# Electgpl_F883-6_THT_Rev1.net
KiCad netlist of a schematic drawn in EAGLE
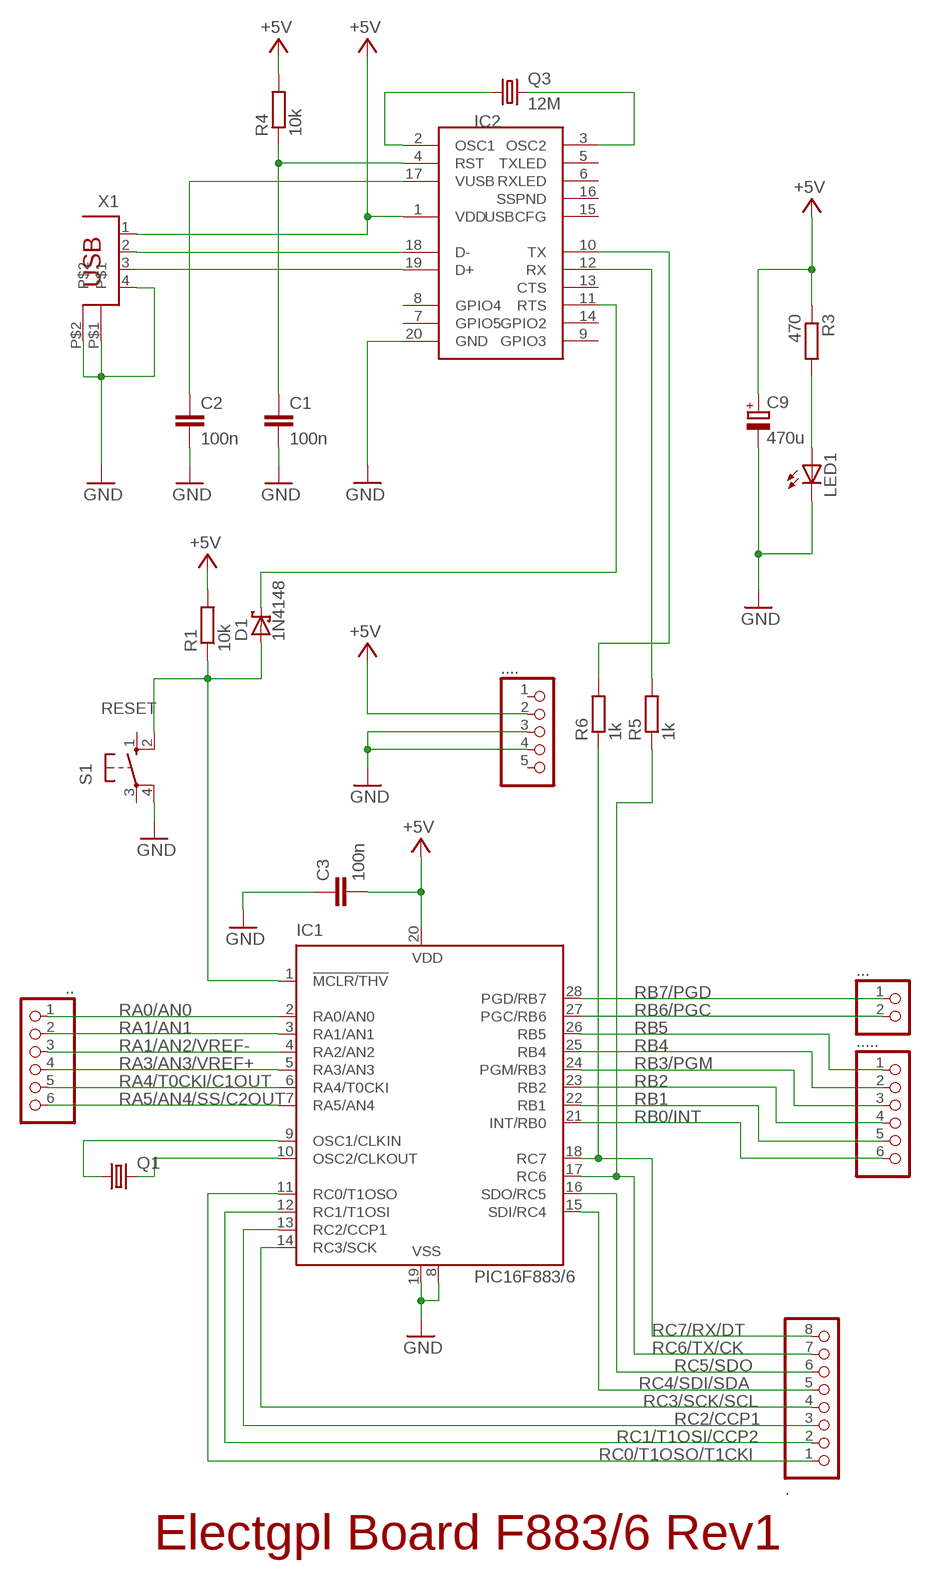
[diagram p0: schematic, sheet 1]

(export (version "E")
  (design (tool "Eeschema 10.0.6"))
  (components
    (comp (ref ".")
      (value "PINHD-1X8")
      (footprint "eagle-import:1X08")
      (libsource (lib "eagle-import") (part "PINHD-1X8"))
    )
    (comp (ref "..")
      (value "PINHD-1X6")
      (footprint "eagle-import:1X06")
      (libsource (lib "eagle-import") (part "PINHD-1X6"))
    )
    (comp (ref "...")
      (value "PINHD-1X2")
      (footprint "eagle-import:1X02")
      (libsource (lib "eagle-import") (part "PINHD-1X2"))
    )
    (comp (ref "....")
      (value "PINHD-1X5")
      (footprint "eagle-import:1X05")
      (libsource (lib "eagle-import") (part "PINHD-1X5"))
    )
    (comp (ref ".....")
      (value "PINHD-1X6")
      (footprint "eagle-import:1X06")
      (libsource (lib "eagle-import") (part "PINHD-1X6"))
    )
    (comp (ref "C1")
      (value "100n")
      (footprint "eagle-import:C025-024X044")
      (libsource (lib "eagle-import") (part "C-EU025-024X044"))
    )
    (comp (ref "C2")
      (value "100n")
      (footprint "eagle-import:C025-024X044")
      (libsource (lib "eagle-import") (part "C-EU025-024X044"))
    )
    (comp (ref "C3")
      (value "100n")
      (footprint "eagle-import:C025-024X044")
      (libsource (lib "eagle-import") (part "C-EU025-024X044"))
    )
    (comp (ref "C9")
      (value "470u")
      (footprint "eagle-import:E3,5-10")
      (libsource (lib "eagle-import") (part "CPOL-EUE3.5-10"))
    )
    (comp (ref "D1")
      (value "1N4148")
      (footprint "eagle-import:DO35-7")
      (libsource (lib "eagle-import") (part "SCHOTTKY-DIODEDO35-7"))
    )
    (comp (ref "IC1")
      (value "PIC16F883/6")
      (footprint "eagle-import:DIL28-3")
      (libsource (lib "eagle-import") (part "PIC16876P"))
    )
    (comp (ref "IC2")
      (value "MCP2200SOIC20")
      (footprint "eagle-import:SOIC20")
      (libsource (lib "eagle-import") (part "MCP2200SOIC20"))
    )
    (comp (ref "LED1")
      (value "LED3MM")
      (footprint "eagle-import:LED3MM")
      (libsource (lib "eagle-import") (part "LED3MM"))
    )
    (comp (ref "Q1")
      (value "CRYSTALHC49S")
      (footprint "eagle-import:HC49_S")
      (libsource (lib "eagle-import") (part "CRYSTALHC49S"))
    )
    (comp (ref "Q3")
      (value "12M")
      (footprint "eagle-import:HC49_S")
      (libsource (lib "eagle-import") (part "CRYSTALHC49S"))
    )
    (comp (ref "R1")
      (value "10k")
      (footprint "eagle-import:0204_5")
      (libsource (lib "eagle-import") (part "R-EU_0204/5"))
    )
    (comp (ref "R3")
      (value "470")
      (footprint "eagle-import:0204_5")
      (libsource (lib "eagle-import") (part "R-EU_0204/5"))
    )
    (comp (ref "R4")
      (value "10k")
      (footprint "eagle-import:0204_5")
      (libsource (lib "eagle-import") (part "R-EU_0204/5"))
    )
    (comp (ref "R5")
      (value "1k")
      (footprint "eagle-import:0204_5")
      (libsource (lib "eagle-import") (part "R-EU_0204/5"))
    )
    (comp (ref "R6")
      (value "1k")
      (footprint "eagle-import:0204_5")
      (libsource (lib "eagle-import") (part "R-EU_0204/5"))
    )
    (comp (ref "S1")
      (value "10-XX")
      (footprint "eagle-import:B3F-10XX")
      (fields (field (name "MPN") "B3F-1000"))
      (libsource (lib "eagle-import") (part "10-XX"))
    )
    (comp (ref "X1")
      (value "PN61729")
      (footprint "eagle-import:PN61729")
      (libsource (lib "eagle-import") (part "PN61729"))
    )
  )
  (nets
    (net (code "1") (name "+5V") (class "Default")
      (node (ref "....") (pin "2") (pinfunction "2_2") (pintype "passive"))
      (node (ref "C3") (pin "2") (pinfunction "2_2") (pintype "passive"))
      (node (ref "C9") (pin "+") (pinfunction "+_+") (pintype "passive"))
      (node (ref "IC1") (pin "20") (pinfunction "VDD_20") (pintype "power_in"))
      (node (ref "IC2") (pin "1") (pinfunction "VDD_1") (pintype "bidirectional"))
      (node (ref "R1") (pin "2") (pinfunction "2_2") (pintype "passive"))
      (node (ref "R3") (pin "1") (pinfunction "1_1") (pintype "passive"))
      (node (ref "R4") (pin "2") (pinfunction "2_2") (pintype "passive"))
      (node (ref "X1") (pin "1") (pinfunction "1_1") (pintype "bidirectional"))
    )
    (net (code "2") (name "/RA0{slash}AN0") (class "Default")
      (node (ref "..") (pin "1") (pinfunction "1_1") (pintype "passive"))
      (node (ref "IC1") (pin "2") (pinfunction "RA0/AN0_2") (pintype "bidirectional"))
    )
    (net (code "3") (name "/RA1{slash}AN1") (class "Default")
      (node (ref "..") (pin "2") (pinfunction "2_2") (pintype "passive"))
      (node (ref "IC1") (pin "3") (pinfunction "RA1/AN1_3") (pintype "bidirectional"))
    )
    (net (code "4") (name "/RA1{slash}AN2{slash}VREF-") (class "Default")
      (node (ref "..") (pin "3") (pinfunction "3_3") (pintype "passive"))
      (node (ref "IC1") (pin "4") (pinfunction "RA2/AN2_4") (pintype "bidirectional"))
    )
    (net (code "5") (name "/RA3{slash}AN3{slash}VREF+") (class "Default")
      (node (ref "..") (pin "4") (pinfunction "4_4") (pintype "passive"))
      (node (ref "IC1") (pin "5") (pinfunction "RA3/AN3_5") (pintype "bidirectional"))
    )
    (net (code "6") (name "/RA4{slash}T0CKI{slash}C1OUT") (class "Default")
      (node (ref "..") (pin "5") (pinfunction "5_5") (pintype "passive"))
      (node (ref "IC1") (pin "6") (pinfunction "RA4/T0CKI_6") (pintype "bidirectional"))
    )
    (net (code "7") (name "/RA5{slash}AN4{slash}SS{slash}C2OUT") (class "Default")
      (node (ref "..") (pin "6") (pinfunction "6_6") (pintype "passive"))
      (node (ref "IC1") (pin "7") (pinfunction "RA5/AN4_7") (pintype "bidirectional"))
    )
    (net (code "8") (name "/RB0{slash}INT") (class "Default")
      (node (ref ".....") (pin "6") (pinfunction "6_6") (pintype "passive"))
      (node (ref "IC1") (pin "21") (pinfunction "INT/RB0_21") (pintype "bidirectional"))
    )
    (net (code "9") (name "/RB1") (class "Default")
      (node (ref ".....") (pin "5") (pinfunction "5_5") (pintype "passive"))
      (node (ref "IC1") (pin "22") (pinfunction "RB1_22") (pintype "bidirectional"))
    )
    (net (code "10") (name "/RB2") (class "Default")
      (node (ref ".....") (pin "4") (pinfunction "4_4") (pintype "passive"))
      (node (ref "IC1") (pin "23") (pinfunction "RB2_23") (pintype "bidirectional"))
    )
    (net (code "11") (name "/RB3{slash}PGM") (class "Default")
      (node (ref ".....") (pin "3") (pinfunction "3_3") (pintype "passive"))
      (node (ref "IC1") (pin "24") (pinfunction "PGM/RB3_24") (pintype "bidirectional"))
    )
    (net (code "12") (name "/RB4") (class "Default")
      (node (ref ".....") (pin "2") (pinfunction "2_2") (pintype "passive"))
      (node (ref "IC1") (pin "25") (pinfunction "RB4_25") (pintype "bidirectional"))
    )
    (net (code "13") (name "/RB5") (class "Default")
      (node (ref ".....") (pin "1") (pinfunction "1_1") (pintype "passive"))
      (node (ref "IC1") (pin "26") (pinfunction "RB5_26") (pintype "bidirectional"))
    )
    (net (code "14") (name "/RB6{slash}PGC") (class "Default")
      (node (ref "...") (pin "2") (pinfunction "2_2") (pintype "passive"))
      (node (ref "IC1") (pin "27") (pinfunction "PGC/RB6_27") (pintype "bidirectional"))
    )
    (net (code "15") (name "/RB7{slash}PGD") (class "Default")
      (node (ref "...") (pin "1") (pinfunction "1_1") (pintype "passive"))
      (node (ref "IC1") (pin "28") (pinfunction "PGD/RB7_28") (pintype "bidirectional"))
    )
    (net (code "16") (name "/RC0{slash}T1OSO{slash}T1CKI") (class "Default")
      (node (ref ".") (pin "1") (pinfunction "1_1") (pintype "passive"))
      (node (ref "IC1") (pin "11") (pinfunction "RC0/T1OSO_11") (pintype "bidirectional"))
    )
    (net (code "17") (name "/RC1{slash}T1OSI{slash}CCP2") (class "Default")
      (node (ref ".") (pin "2") (pinfunction "2_2") (pintype "passive"))
      (node (ref "IC1") (pin "12") (pinfunction "RC1/T1OSI_12") (pintype "bidirectional"))
    )
    (net (code "18") (name "/RC2{slash}CCP1") (class "Default")
      (node (ref ".") (pin "3") (pinfunction "3_3") (pintype "passive"))
      (node (ref "IC1") (pin "13") (pinfunction "RC2/CCP1_13") (pintype "bidirectional"))
    )
    (net (code "19") (name "/RC3{slash}SCK{slash}SCL") (class "Default")
      (node (ref ".") (pin "4") (pinfunction "4_4") (pintype "passive"))
      (node (ref "IC1") (pin "14") (pinfunction "RC3/SCK_14") (pintype "bidirectional"))
    )
    (net (code "20") (name "/RC4{slash}SDI{slash}SDA") (class "Default")
      (node (ref ".") (pin "5") (pinfunction "5_5") (pintype "passive"))
      (node (ref "IC1") (pin "15") (pinfunction "SDI/RC4_15") (pintype "bidirectional"))
    )
    (net (code "21") (name "/RC5{slash}SDO") (class "Default")
      (node (ref ".") (pin "6") (pinfunction "6_6") (pintype "passive"))
      (node (ref "IC1") (pin "16") (pinfunction "SDO/RC5_16") (pintype "bidirectional"))
    )
    (net (code "22") (name "/RC6{slash}TX{slash}CK") (class "Default")
      (node (ref ".") (pin "7") (pinfunction "7_7") (pintype "passive"))
      (node (ref "IC1") (pin "17") (pinfunction "RC6_17") (pintype "bidirectional"))
      (node (ref "R5") (pin "1") (pinfunction "1_1") (pintype "passive"))
    )
    (net (code "23") (name "/RC7{slash}RX{slash}DT") (class "Default")
      (node (ref ".") (pin "8") (pinfunction "8_8") (pintype "passive"))
      (node (ref "IC1") (pin "18") (pinfunction "RC7_18") (pintype "bidirectional"))
      (node (ref "R6") (pin "1") (pinfunction "1_1") (pintype "passive"))
    )
    (net (code "24") (name "/RESET") (class "Default")
      (node (ref "D1") (pin "A") (pinfunction "A_A") (pintype "passive"))
      (node (ref "IC1") (pin "1") (pinfunction "~{MCLR/THV}_1") (pintype "input"))
      (node (ref "R1") (pin "1") (pinfunction "1_1") (pintype "passive"))
      (node (ref "S1") (pin "2") (pinfunction "S1_2") (pintype "passive"))
    )
    (net (code "25") (name "GND") (class "Default")
      (node (ref "....") (pin "3") (pinfunction "3_3") (pintype "passive"))
      (node (ref "....") (pin "4") (pinfunction "4_4") (pintype "passive"))
      (node (ref "C1") (pin "2") (pinfunction "2_2") (pintype "passive"))
      (node (ref "C2") (pin "2") (pinfunction "2_2") (pintype "passive"))
      (node (ref "C3") (pin "1") (pinfunction "1_1") (pintype "passive"))
      (node (ref "C9") (pin "-") (pinfunction "-_-") (pintype "passive"))
      (node (ref "IC1") (pin "19") (pinfunction "VSS_19") (pintype "power_in"))
      (node (ref "IC1") (pin "8") (pinfunction "VSS_8") (pintype "power_in"))
      (node (ref "IC2") (pin "20") (pinfunction "GND_20") (pintype "bidirectional"))
      (node (ref "LED1") (pin "K") (pinfunction "C_K") (pintype "passive"))
      (node (ref "S1") (pin "4") (pinfunction "P1_4") (pintype "passive"))
      (node (ref "X1") (pin "4") (pinfunction "4_4") (pintype "bidirectional"))
      (node (ref "X1") (pin "P$1") (pinfunction "P$1_P$1") (pintype "bidirectional"))
      (node (ref "X1") (pin "P$2") (pinfunction "P$2_P$2") (pintype "bidirectional"))
    )
    (net (code "26") (name "Net-(IC1-OSC1{slash}CLKIN)") (class "Default")
      (node (ref "IC1") (pin "9") (pinfunction "OSC1/CLKIN_9") (pintype "input"))
      (node (ref "Q1") (pin "1") (pinfunction "1_1") (pintype "passive"))
    )
    (net (code "27") (name "Net-(IC1-OSC2{slash}CLKOUT)") (class "Default")
      (node (ref "IC1") (pin "10") (pinfunction "OSC2/CLKOUT_10") (pintype "output"))
      (node (ref "Q1") (pin "2") (pinfunction "2_2") (pintype "passive"))
    )
    (net (code "28") (name "Net-(IC2-D+)") (class "Default")
      (node (ref "IC2") (pin "19") (pinfunction "D+_19") (pintype "bidirectional"))
      (node (ref "X1") (pin "3") (pinfunction "3_3") (pintype "bidirectional"))
    )
    (net (code "29") (name "Net-(IC2-D-)") (class "Default")
      (node (ref "IC2") (pin "18") (pinfunction "D-_18") (pintype "bidirectional"))
      (node (ref "X1") (pin "2") (pinfunction "2_2") (pintype "bidirectional"))
    )
    (net (code "30") (name "Net-(IC2-OSC1)") (class "Default")
      (node (ref "IC2") (pin "2") (pinfunction "OSC1_2") (pintype "bidirectional"))
      (node (ref "Q3") (pin "1") (pinfunction "1_1") (pintype "passive"))
    )
    (net (code "31") (name "Net-(IC2-OSC2)") (class "Default")
      (node (ref "IC2") (pin "3") (pinfunction "OSC2_3") (pintype "bidirectional"))
      (node (ref "Q3") (pin "2") (pinfunction "2_2") (pintype "passive"))
    )
    (net (code "32") (name "Net-(IC2-RST)") (class "Default")
      (node (ref "C1") (pin "1") (pinfunction "1_1") (pintype "passive"))
      (node (ref "IC2") (pin "4") (pinfunction "RST_4") (pintype "bidirectional"))
      (node (ref "R4") (pin "1") (pinfunction "1_1") (pintype "passive"))
    )
    (net (code "33") (name "Net-(IC2-RTS)") (class "Default")
      (node (ref "D1") (pin "C") (pinfunction "C_C") (pintype "passive"))
      (node (ref "IC2") (pin "11") (pinfunction "RTS_11") (pintype "bidirectional"))
    )
    (net (code "34") (name "Net-(IC2-RX)") (class "Default")
      (node (ref "IC2") (pin "12") (pinfunction "RX_12") (pintype "bidirectional"))
      (node (ref "R5") (pin "2") (pinfunction "2_2") (pintype "passive"))
    )
    (net (code "35") (name "Net-(IC2-TX)") (class "Default")
      (node (ref "IC2") (pin "10") (pinfunction "TX_10") (pintype "bidirectional"))
      (node (ref "R6") (pin "2") (pinfunction "2_2") (pintype "passive"))
    )
    (net (code "36") (name "Net-(IC2-VUSB)") (class "Default")
      (node (ref "C2") (pin "1") (pinfunction "1_1") (pintype "passive"))
      (node (ref "IC2") (pin "17") (pinfunction "VUSB_17") (pintype "bidirectional"))
    )
    (net (code "37") (name "Net-(LED1-PadA)") (class "Default")
      (node (ref "LED1") (pin "A") (pinfunction "A_A") (pintype "passive"))
      (node (ref "R3") (pin "2") (pinfunction "2_2") (pintype "passive"))
    )
    (net (code "38") (name "unconnected-(....-Pad1)") (class "Default")
      (node (ref "....") (pin "1") (pinfunction "1_1") (pintype "passive"))
    )
    (net (code "39") (name "unconnected-(....-Pad5)") (class "Default")
      (node (ref "....") (pin "5") (pinfunction "5_5") (pintype "passive"))
    )
    (net (code "40") (name "unconnected-(IC2-CTS-Pad13)") (class "Default")
      (node (ref "IC2") (pin "13") (pinfunction "CTS_13") (pintype "bidirectional"))
    )
    (net (code "41") (name "unconnected-(IC2-GPIO2-Pad14)") (class "Default")
      (node (ref "IC2") (pin "14") (pinfunction "GPIO2_14") (pintype "bidirectional"))
    )
    (net (code "42") (name "unconnected-(IC2-GPIO3-Pad9)") (class "Default")
      (node (ref "IC2") (pin "9") (pinfunction "GPIO3_9") (pintype "bidirectional"))
    )
    (net (code "43") (name "unconnected-(IC2-GPIO4-Pad8)") (class "Default")
      (node (ref "IC2") (pin "8") (pinfunction "GPIO4_8") (pintype "bidirectional"))
    )
    (net (code "44") (name "unconnected-(IC2-GPIO5-Pad7)") (class "Default")
      (node (ref "IC2") (pin "7") (pinfunction "GPIO5_7") (pintype "bidirectional"))
    )
    (net (code "45") (name "unconnected-(IC2-RXLED-Pad6)") (class "Default")
      (node (ref "IC2") (pin "6") (pinfunction "RXLED_6") (pintype "bidirectional"))
    )
    (net (code "46") (name "unconnected-(IC2-SSPND-Pad16)") (class "Default")
      (node (ref "IC2") (pin "16") (pinfunction "SSPND_16") (pintype "bidirectional"))
    )
    (net (code "47") (name "unconnected-(IC2-TXLED-Pad5)") (class "Default")
      (node (ref "IC2") (pin "5") (pinfunction "TXLED_5") (pintype "bidirectional"))
    )
    (net (code "48") (name "unconnected-(IC2-USBCFG-Pad15)") (class "Default")
      (node (ref "IC2") (pin "15") (pinfunction "USBCFG_15") (pintype "bidirectional"))
    )
    (net (code "49") (name "unconnected-(S1-P-Pad3)") (class "Default")
      (node (ref "S1") (pin "3") (pinfunction "P_3") (pintype "passive"))
    )
    (net (code "50") (name "unconnected-(S1-S-Pad1)") (class "Default")
      (node (ref "S1") (pin "1") (pinfunction "S_1") (pintype "passive"))
    )
  )
)
